# 100_Motor_Mosfet_RGB.net
KiCad netlist of a schematic drawn in Altium Designer
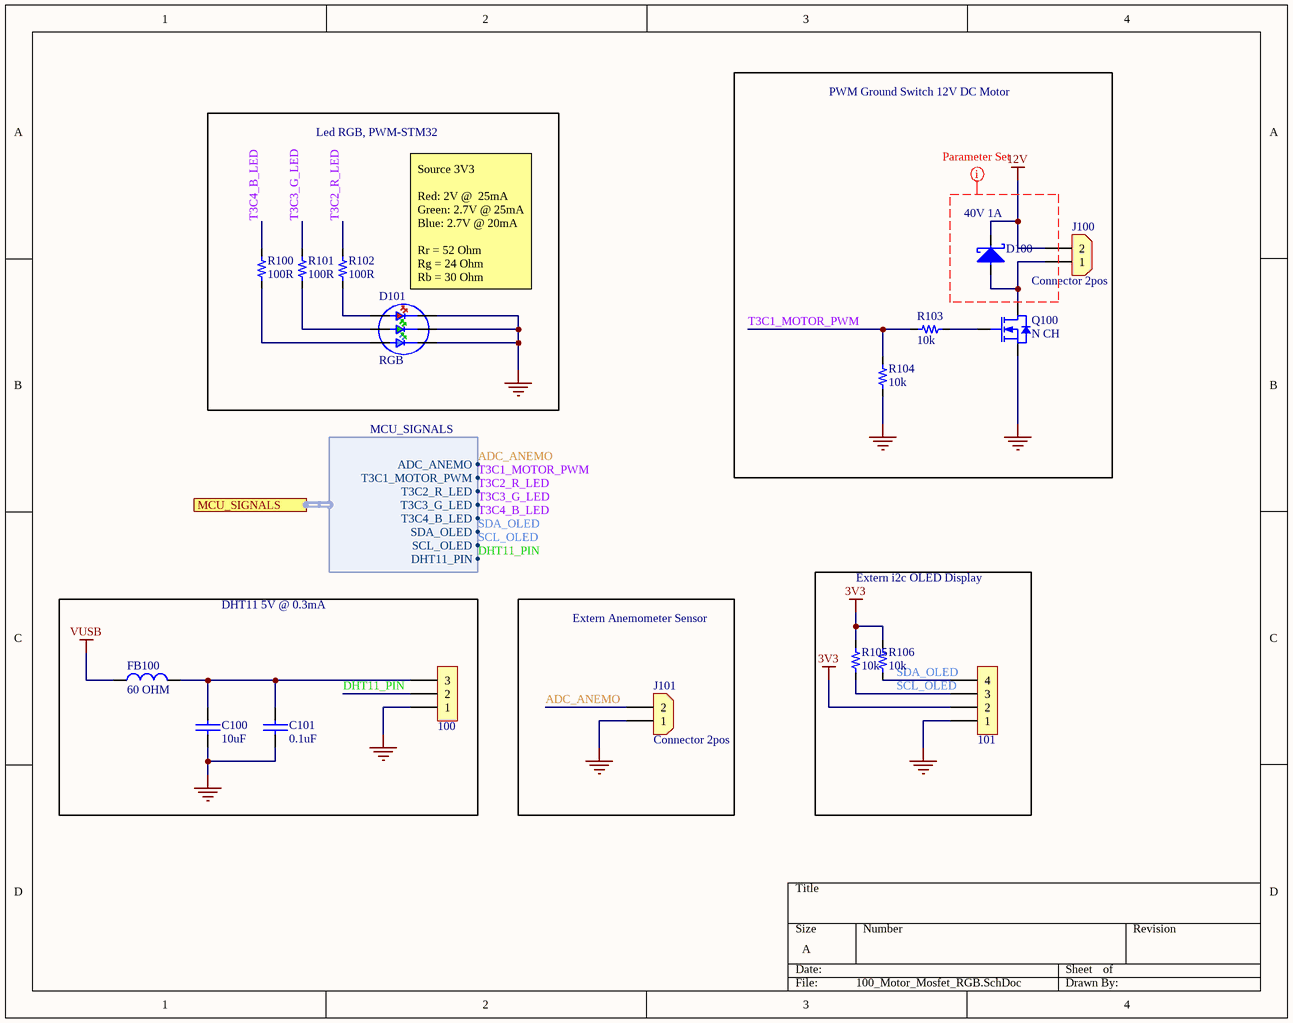
[diagram p0: 100_Motor_Mosfet_RGB.SchDoc]

(export (version "E")
  (design (tool "Eeschema 10.0.6"))
  (components
    (comp (ref "100")
      (value "3x1")
      (footprint "H_3X1_TH_100mil")
      (description "H_Male_3x1_TH_100mil")
      (libsource (lib "shared_lib") (part "H_Male_3x1_TH_100mil"))
    )
    (comp (ref "101")
      (value "4x1")
      (footprint "H_4x1_TH_2.54mm")
      (description "H_Male_4x1_TH_100mil")
      (libsource (lib "shared_lib") (part "H_Male_4x1_TH_100mil"))
    )
    (comp (ref "C100")
      (value "10uF")
      (footprint "0805_cap")
      (description "25V 10uF X5R ±10% 0805 Multilayer Ceramic Capacitors MLCC - SMD/SMT ROHS")
      (fields
        (field (name "MANUFACTURER") "Samsung Electro-Mechanics")
        (field (name "MANUFACTURER PART NUMBER") "CL21A106KAYNNNE")
      )
      (libsource (lib "shared_lib") (part "Cap_10uF_0805_25V_"))
    )
    (comp (ref "C101")
      (value "0.1uF")
      (footprint "0603_cap")
      (description "50V 100nF Y5V -20%~+80% 0603 Multilayer Ceramic Capacitors MLCC - SMD/SMT ROHS")
      (fields
        (field (name "MANUFACTURER") "Walsin Tech Corp")
        (field (name "MANUFACTURER PART NUMBER") "0603F104Z500CT")
      )
      (libsource (lib "shared_lib") (part "Cap_0.1uF_0603_50V"))
    )
    (comp (ref "D100")
      (value "40V 1A")
      (footprint "SOD_123")
      (description "DIODE SCHOTTKY 40V 1A SOD123F")
      (fields
        (field (name "MANUFACTURER") "Shanghai Prisemi Elec")
        (field (name "MANUFACTURER PART NUMBER") "PSBD1DF40V1H")
      )
      (libsource (lib "shared_lib") (part "D_Schottky_40V_1A_SOD_123F"))
    )
    (comp (ref "D101")
      (value "RGB")
      (footprint "RGB_NS_3.5X3.7")
      (description "-30℃~+85℃ RGB 110° 3535(mm) Light Emitting Diodes (LED) ROHS")
      (fields
        (field (name "MANUFACTURER") "Foshan NationStar Optoelectronics")
        (field (name "MANUFACTURER PART NUMBER") "RS-3535MWAM")
      )
      (libsource (lib "shared_lib") (part "LED_RGB_3535_SMD"))
    )
    (comp (ref "FB100")
      (value "60 OHM")
      (footprint "0603_fb")
      (description "2A 1 100mΩ 60Ω@100MHz ±25% 0603 Ferrite Beads ROHS")
      (fields
        (field (name "MANUFACTURER") "TAI-TECH")
        (field (name "MANUFACTURER PART NUMBER") "HCB1608KF-600T20")
      )
      (libsource (lib "shared_lib") (part "FB_60_0603_2A"))
    )
    (comp (ref "J100")
      (value "Connector 2pos")
      (footprint "CON_2x1_TH_5MM")
      (description "2POS 5MM")
      (fields (field (name "MANUFACTURER") "JILN") (field (name "MANUFACTURER PART NUMBER") "JL126-50002G01"))
      (libsource (lib "shared_lib") (part "Con_2x1_TH_5mm"))
    )
    (comp (ref "J101")
      (value "Connector 2pos")
      (footprint "CON_2x1_TH_5MM")
      (description "2POS 5MM")
      (fields (field (name "MANUFACTURER") "JILN") (field (name "MANUFACTURER PART NUMBER") "JL126-50002G01"))
      (libsource (lib "shared_lib") (part "Con_2x1_TH_5mm"))
    )
    (comp (ref "Q100")
      (value "N CH")
      (footprint "SOT_23_3")
      (description "MOSFET N-CH 20V SOT23")
      (fields (field (name "MANUFACTURER") "Doeshare") (field (name "MANUFACTURER PART NUMBER") "DN2302S"))
      (libsource (lib "shared_lib") (part "Q_NFET_20V_3.2A_SOT23"))
    )
    (comp (ref "R100")
      (value "100R")
      (footprint "0603_res")
      (description "RES SMD 100R OHM 5% 1/10W 0603")
      (fields
        (field (name "MANUFACTURER") "FOJAN")
        (field (name "MANUFACTURER PART NUMBER") "FRC0603J101 TS")
      )
      (libsource (lib "shared_lib") (part "Res_100R_0603_1/10W"))
    )
    (comp (ref "R101")
      (value "100R")
      (footprint "0603_res")
      (description "RES SMD 100R OHM 5% 1/10W 0603")
      (fields
        (field (name "MANUFACTURER") "FOJAN")
        (field (name "MANUFACTURER PART NUMBER") "FRC0603J101 TS")
      )
      (libsource (lib "shared_lib") (part "Res_100R_0603_1/10W"))
    )
    (comp (ref "R102")
      (value "100R")
      (footprint "0603_res")
      (description "RES SMD 100R OHM 5% 1/10W 0603")
      (fields
        (field (name "MANUFACTURER") "FOJAN")
        (field (name "MANUFACTURER PART NUMBER") "FRC0603J101 TS")
      )
      (libsource (lib "shared_lib") (part "Res_100R_0603_1/10W"))
    )
    (comp (ref "R103")
      (value "10k")
      (footprint "0603_res")
      (description "RES SMD 10k OHM 5% 1/10W 0603")
      (fields (field (name "MANUFACTURER") "FOJAN") (field (name "MANUFACTURER PART NUMBER") "FRC0603J103TS"))
      (libsource (lib "shared_lib") (part "Res_10k_0603_1/10W"))
    )
    (comp (ref "R104")
      (value "10k")
      (footprint "0603_res")
      (description "RES SMD 10k OHM 5% 1/10W 0603")
      (fields (field (name "MANUFACTURER") "FOJAN") (field (name "MANUFACTURER PART NUMBER") "FRC0603J103TS"))
      (libsource (lib "shared_lib") (part "Res_10k_0603_1/10W"))
    )
    (comp (ref "R105")
      (value "10k")
      (footprint "0603_res")
      (description "RES SMD 10k OHM 5% 1/10W 0603")
      (fields (field (name "MANUFACTURER") "FOJAN") (field (name "MANUFACTURER PART NUMBER") "FRC0603J103TS"))
      (libsource (lib "shared_lib") (part "Res_10k_0603_1/10W"))
    )
    (comp (ref "R106")
      (value "10k")
      (footprint "0603_res")
      (description "RES SMD 10k OHM 5% 1/10W 0603")
      (fields (field (name "MANUFACTURER") "FOJAN") (field (name "MANUFACTURER PART NUMBER") "FRC0603J103TS"))
      (libsource (lib "shared_lib") (part "Res_10k_0603_1/10W"))
    )
  )
  (nets
    (net (code "2") (name "/ADC_ANEMO") (class "Default")
      (node (ref "J101") (pin "2") (pinfunction "2_2") (pintype "passive"))
    )
    (net (code "3") (name "/DHT11_PIN") (class "Default")
      (node (ref "100") (pin "2") (pinfunction "2_2") (pintype "passive"))
    )
    (net (code "4") (name "/SCL_OLED") (class "Default")
      (node (ref "101") (pin "3") (pinfunction "3_3") (pintype "passive"))
      (node (ref "R105") (pin "1") (pinfunction "1_1") (pintype "passive"))
    )
    (net (code "5") (name "/SDA_OLED") (class "Default")
      (node (ref "101") (pin "4") (pinfunction "4_4") (pintype "passive"))
      (node (ref "R106") (pin "1") (pinfunction "1_1") (pintype "passive"))
    )
    (net (code "6") (name "/T3C1_MOTOR_PWM") (class "Default")
      (node (ref "R103") (pin "2") (pinfunction "2_2") (pintype "passive"))
      (node (ref "R104") (pin "2") (pinfunction "2_2") (pintype "passive"))
    )
    (net (code "7") (name "/T3C2_R_LED") (class "Default")
      (node (ref "R102") (pin "2") (pinfunction "2_2") (pintype "passive"))
    )
    (net (code "8") (name "/T3C3_G_LED") (class "Default")
      (node (ref "R101") (pin "2") (pinfunction "2_2") (pintype "passive"))
    )
    (net (code "9") (name "/T3C4_B_LED") (class "Default")
      (node (ref "R100") (pin "2") (pinfunction "2_2") (pintype "passive"))
    )
    (net (code "11") (name "3V3") (class "Default")
      (node (ref "101") (pin "2") (pinfunction "2_2") (pintype "passive"))
      (node (ref "R105") (pin "2") (pinfunction "2_2") (pintype "passive"))
      (node (ref "R106") (pin "2") (pinfunction "2_2") (pintype "passive"))
    )
    (net (code "12") (name "12V") (class "Default")
      (node (ref "D100") (pin "1") (pinfunction "1_1") (pintype "passive"))
      (node (ref "J100") (pin "2") (pinfunction "2_2") (pintype "passive"))
    )
    (net (code "13") (name "GND") (class "Default")
      (node (ref "100") (pin "1") (pinfunction "1_1") (pintype "passive"))
      (node (ref "101") (pin "1") (pinfunction "1_1") (pintype "passive"))
      (node (ref "C100") (pin "2") (pinfunction "2_2") (pintype "passive"))
      (node (ref "C101") (pin "2") (pinfunction "2_2") (pintype "passive"))
      (node (ref "D101") (pin "1") (pinfunction "1_1") (pintype "passive"))
      (node (ref "D101") (pin "2") (pinfunction "2_2") (pintype "passive"))
      (node (ref "D101") (pin "3") (pinfunction "3_3") (pintype "passive"))
      (node (ref "J101") (pin "1") (pinfunction "1_1") (pintype "passive"))
      (node (ref "Q100") (pin "2") (pinfunction "S_2") (pintype "passive"))
      (node (ref "R104") (pin "1") (pinfunction "1_1") (pintype "passive"))
    )
    (net (code "14") (name "Net-(100-Pad3)") (class "Default")
      (node (ref "100") (pin "3") (pinfunction "3_3") (pintype "passive"))
      (node (ref "C100") (pin "1") (pinfunction "1_1") (pintype "passive"))
      (node (ref "C101") (pin "1") (pinfunction "1_1") (pintype "passive"))
      (node (ref "FB100") (pin "2") (pinfunction "2_2") (pintype "passive"))
    )
    (net (code "15") (name "Net-(D101-Pad4)") (class "Default")
      (node (ref "D101") (pin "4") (pinfunction "4_4") (pintype "passive"))
      (node (ref "R102") (pin "1") (pinfunction "1_1") (pintype "passive"))
    )
    (net (code "16") (name "Net-(D101-Pad5)") (class "Default")
      (node (ref "D101") (pin "5") (pinfunction "5_5") (pintype "passive"))
      (node (ref "R101") (pin "1") (pinfunction "1_1") (pintype "passive"))
    )
    (net (code "17") (name "Net-(D101-Pad6)") (class "Default")
      (node (ref "D101") (pin "6") (pinfunction "6_6") (pintype "passive"))
      (node (ref "R100") (pin "1") (pinfunction "1_1") (pintype "passive"))
    )
    (net (code "18") (name "Net-(Q100-D)") (class "Default")
      (node (ref "D100") (pin "2") (pinfunction "2_2") (pintype "passive"))
      (node (ref "J100") (pin "1") (pinfunction "1_1") (pintype "passive"))
      (node (ref "Q100") (pin "3") (pinfunction "D_3") (pintype "passive"))
    )
    (net (code "19") (name "Net-(Q100-G)") (class "Default")
      (node (ref "Q100") (pin "1") (pinfunction "G_1") (pintype "passive"))
      (node (ref "R103") (pin "1") (pinfunction "1_1") (pintype "passive"))
    )
    (net (code "20") (name "VUSB") (class "Default")
      (node (ref "FB100") (pin "1") (pinfunction "1_1") (pintype "passive"))
    )
  )
)
